# USBSocket_Type7_v1_0.net
KiCad netlist of a schematic drawn in EAGLE
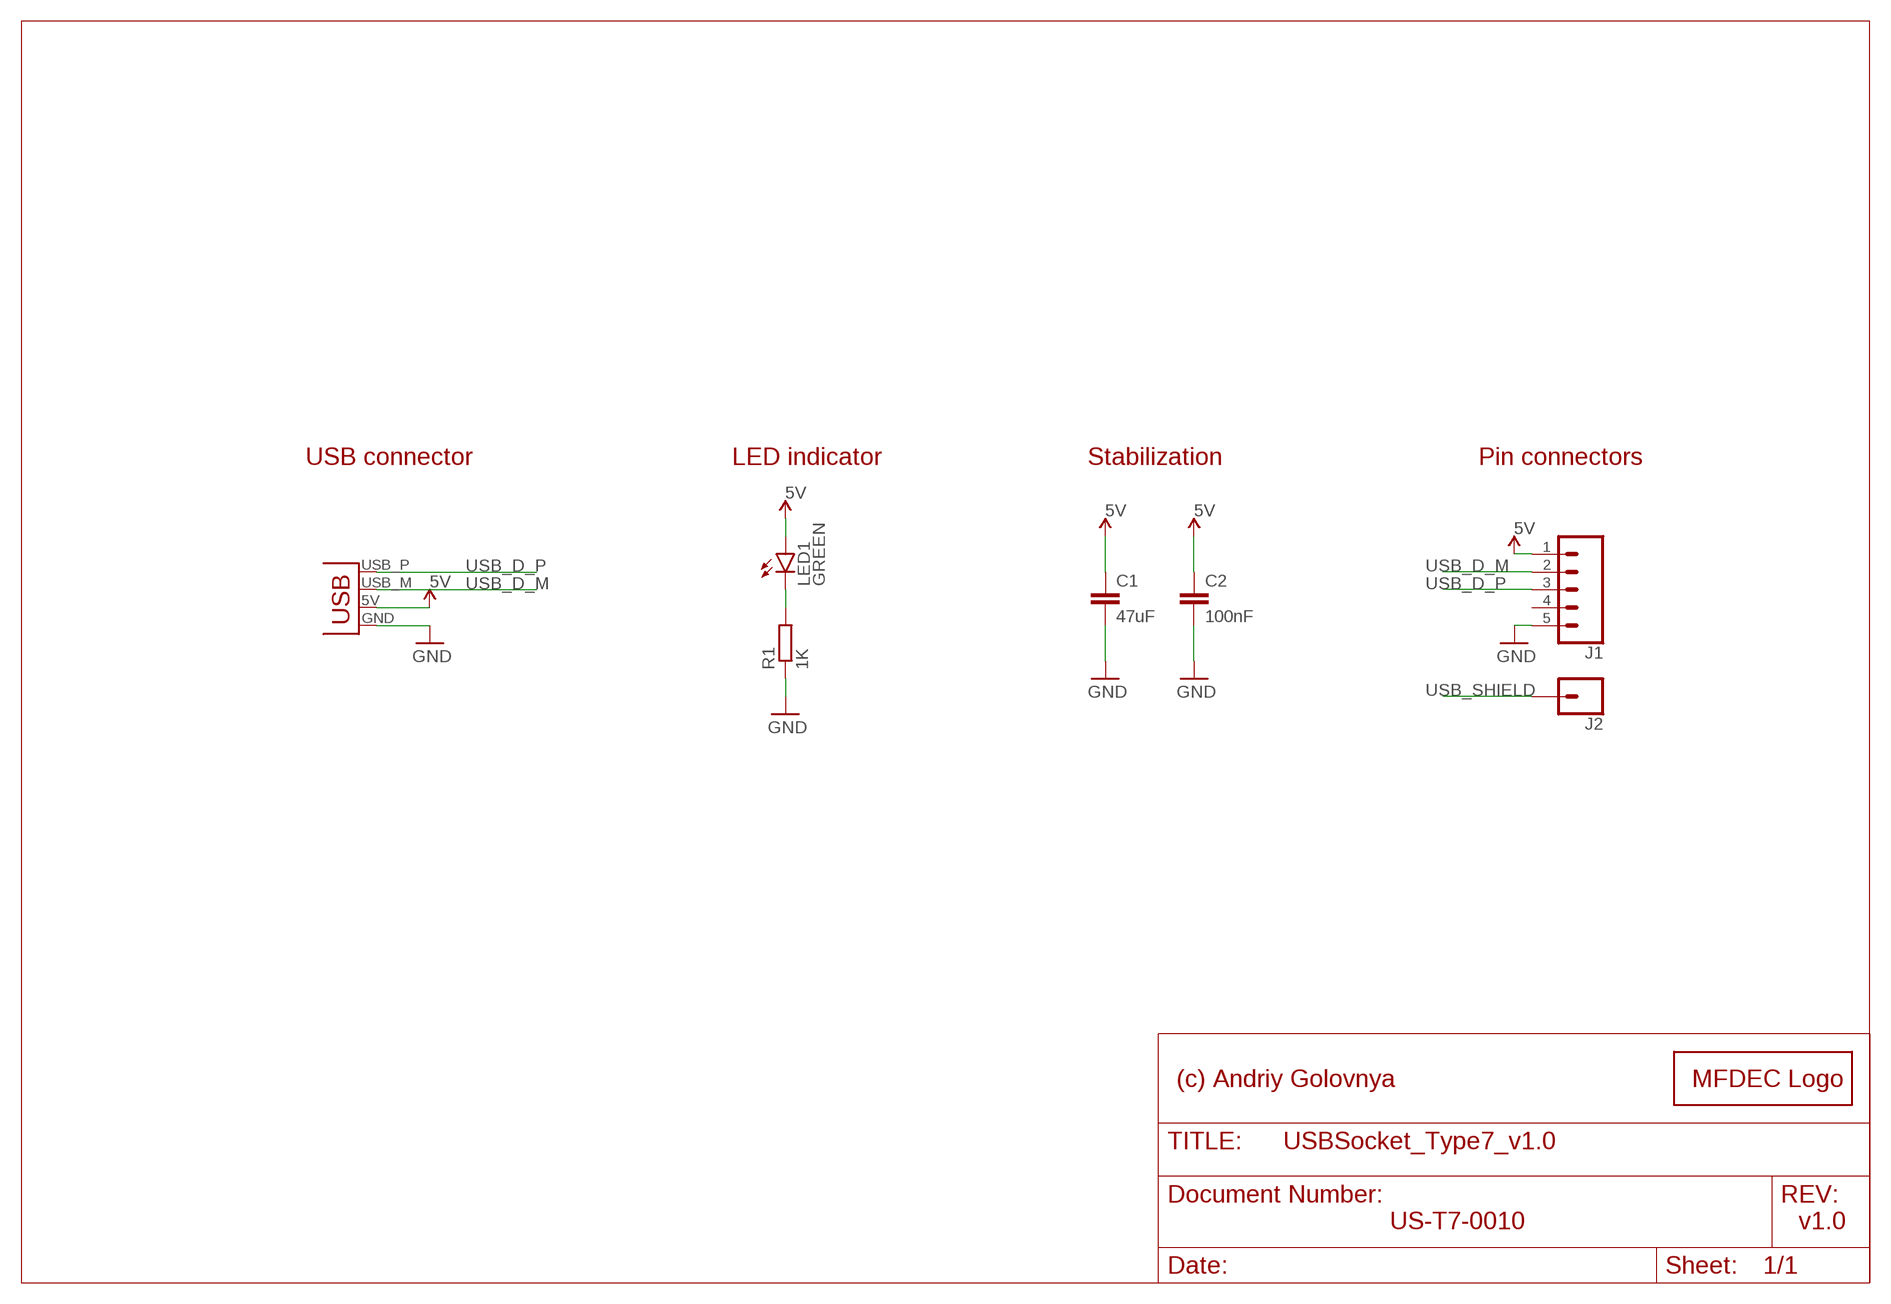
[diagram p0: schematic, sheet 1]

(export (version "E")
  (design (tool "Eeschema 10.0.6"))
  (components
    (comp (ref "C1")
      (value "47uF")
      (footprint "eagle-import:C0805")
      (libsource (lib "eagle-import") (part "C-EUC0805"))
    )
    (comp (ref "C2")
      (value "100nF")
      (footprint "eagle-import:C0402")
      (libsource (lib "eagle-import") (part "C-EUC0402"))
    )
    (comp (ref "J1")
      (value "CONN_05PTH")
      (footprint "eagle-import:1X05")
      (libsource (lib "eagle-import") (part "CONN_05PTH"))
    )
    (comp (ref "J2")
      (value "CONN_01")
      (footprint "eagle-import:1X01")
      (libsource (lib "eagle-import") (part "CONN_01"))
    )
    (comp (ref "LED1")
      (value "GREEN")
      (footprint "eagle-import:SML0603")
      (libsource (lib "eagle-import") (part "LEDSML0603"))
    )
    (comp (ref "LOGO1")
      (value "MFDECLOGO_L_10MM")
      (footprint "eagle-import:MFDEC_L_10MM")
      (libsource (lib "eagle-import") (part "MFDECLOGO_L_10MM"))
    )
    (comp (ref "R1")
      (value "1K")
      (footprint "eagle-import:R0402")
      (libsource (lib "eagle-import") (part "R-EU_R0402"))
    )
    (comp (ref "X1")
      (value "USBPCB")
      (footprint "eagle-import:USB-A-PCB")
      (libsource (lib "eagle-import") (part "USBPCB"))
    )
  )
  (nets
    (net (code "1") (name "/USB_D_M") (class "Default")
      (node (ref "J1") (pin "2") (pinfunction "2_2") (pintype "passive"))
      (node (ref "X1") (pin "USB_M") (pinfunction "D-_USB_M") (pintype "bidirectional"))
    )
    (net (code "2") (name "/USB_D_P") (class "Default")
      (node (ref "J1") (pin "3") (pinfunction "3_3") (pintype "passive"))
      (node (ref "X1") (pin "USB_P") (pinfunction "D+_USB_P") (pintype "bidirectional"))
    )
    (net (code "3") (name "/USB_SHIELD") (class "Default")
      (node (ref "J2") (pin "1") (pinfunction "1_1") (pintype "passive"))
    )
    (net (code "4") (name "5V") (class "Default")
      (node (ref "C1") (pin "1") (pinfunction "1_1") (pintype "passive"))
      (node (ref "C2") (pin "1") (pinfunction "1_1") (pintype "passive"))
      (node (ref "J1") (pin "1") (pinfunction "1_1") (pintype "passive"))
      (node (ref "LED1") (pin "A") (pinfunction "A_A") (pintype "passive"))
      (node (ref "X1") (pin "5V") (pinfunction "VBUS_5V") (pintype "bidirectional"))
    )
    (net (code "5") (name "GND") (class "Default")
      (node (ref "C1") (pin "2") (pinfunction "2_2") (pintype "passive"))
      (node (ref "C2") (pin "2") (pinfunction "2_2") (pintype "passive"))
      (node (ref "J1") (pin "5") (pinfunction "5_5") (pintype "passive"))
      (node (ref "R1") (pin "1") (pinfunction "1_1") (pintype "passive"))
      (node (ref "X1") (pin "GND") (pinfunction "GND_GND") (pintype "bidirectional"))
    )
    (net (code "6") (name "Net-(LED1-PadC)") (class "Default")
      (node (ref "LED1") (pin "C") (pinfunction "C_C") (pintype "passive"))
      (node (ref "R1") (pin "2") (pinfunction "2_2") (pintype "passive"))
    )
    (net (code "7") (name "unconnected-(J1-Pad4)") (class "Default")
      (node (ref "J1") (pin "4") (pinfunction "4_4") (pintype "passive"))
    )
  )
)
